# 5_In_Circuit_Debug_Interface.net
KiCad netlist of a schematic drawn in Altium Designer
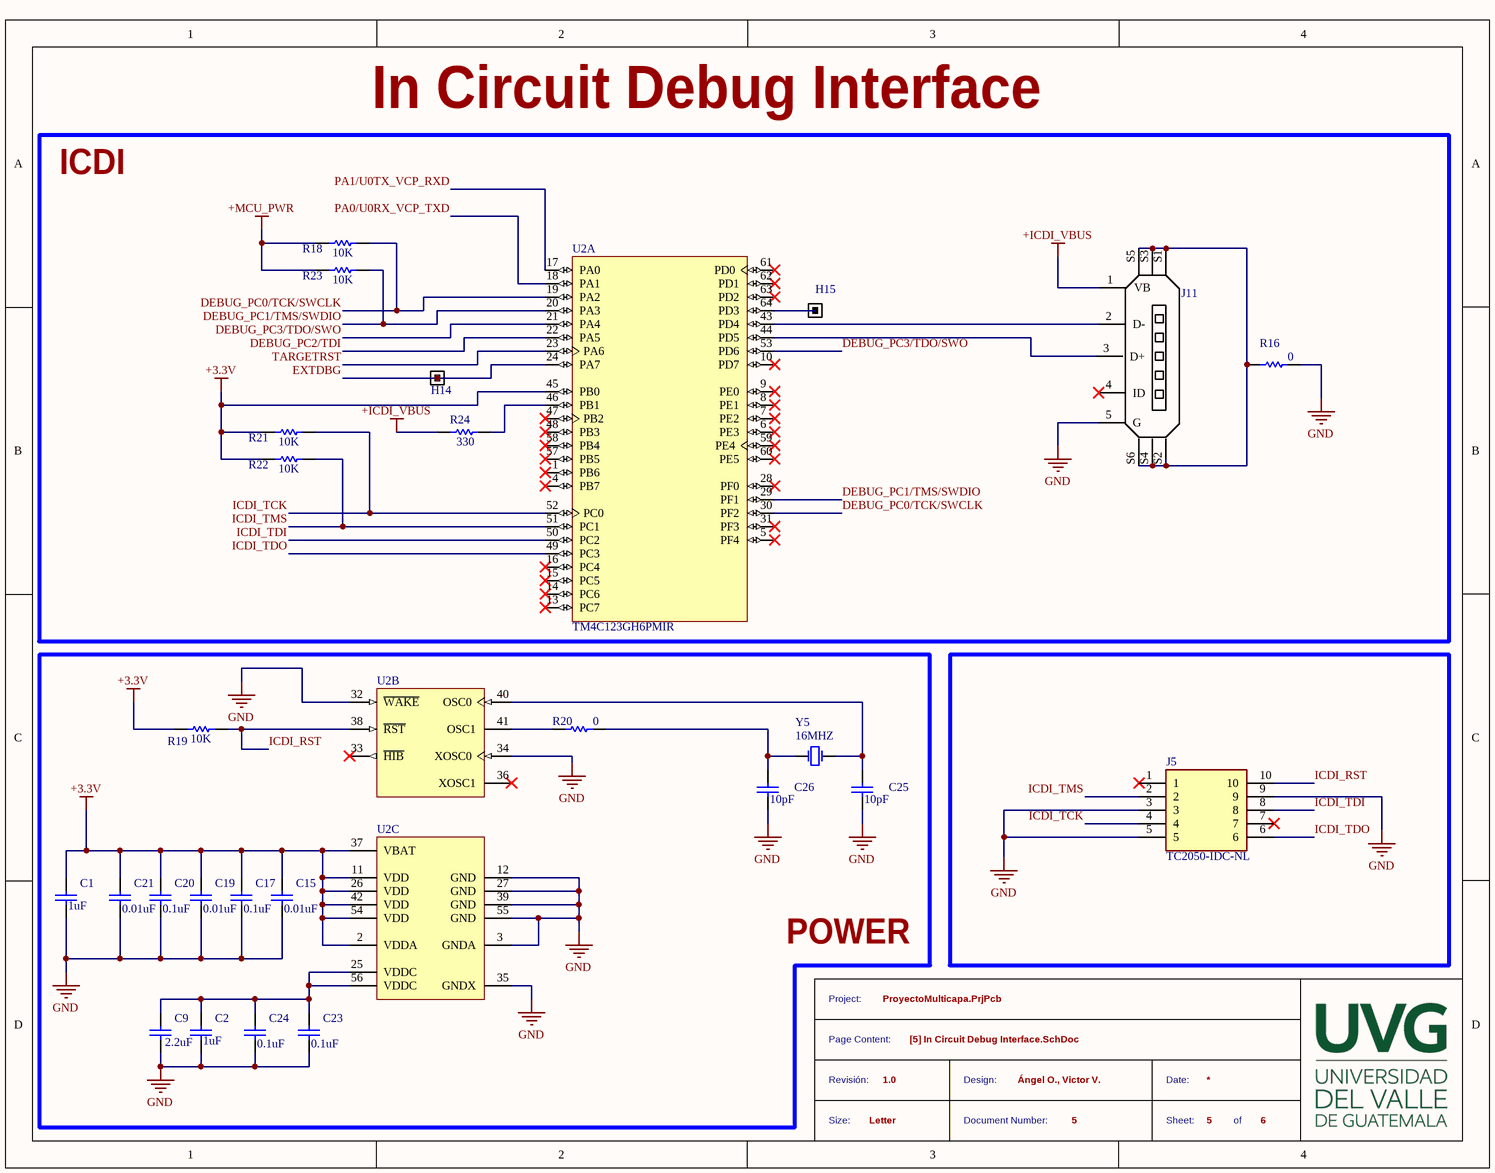
[diagram p0: [5] In Circuit Debug Interface.SchDoc]

(export (version "E")
  (design (tool "Eeschema 10.0.6"))
  (components
    (comp (ref "C1")
      (value "capacitor Johanson Dielectrics Inc")
      (footprint "C0402 imperial")
      (description "Cap Ceramic 1uF 10V X5R 10% SMD 0402 85C T/R")
      (fields
        (field (name "MANUFACTURER") "Johanson")
        (field (name "MANUFACTURER PART NUMBER") "100R07X105KV4T")
      )
      (libsource (lib "Components") (part "100R07X105KV4T"))
    )
    (comp (ref "C2")
      (value "capacitor Johanson Dielectrics Inc")
      (footprint "C0402 imperial")
      (description "Cap Ceramic 1uF 10V X5R 10% SMD 0402 85C T/R")
      (fields
        (field (name "MANUFACTURER") "Johanson")
        (field (name "MANUFACTURER PART NUMBER") "100R07X105KV4T")
      )
      (libsource (lib "Components") (part "100R07X105KV4T"))
    )
    (comp (ref "C9")
      (value "GRM188R61C225KE15D")
      (footprint "CAPC1608X90X35LL10T15")
      (description "Cap Ceramic 2.2uF 16V X5R 10% SMD 0603 85C Paper T/R")
      (fields (field (name "MANUFACTURER") "Murata") (field (name "TOLERANCE") "10%"))
      (libsource (lib "LiberiaTivaC") (part "GRM188R61C225KE15D"))
    )
    (comp (ref "C15")
      (value "EMK105B7103KV-F")
      (footprint "CAPC1005")
      (description "TAIYO YUDEN   EMK105B7103KV-F   CERAMIC CAPACITOR, 0.01UF, 16V, X7R, 10%, 0402, FULL REEL")
      (fields (field (name "MANUFACTURER") "Taiyo Yuden") (field (name "TOLERANCE") "10%"))
      (libsource (lib "LiberiaTivaC") (part "EMK105B7103KV-F"))
    )
    (comp (ref "C17")
      (value "EMK105B7104KV-F")
      (footprint "CAPC1005")
      (fields (field (name "MANUFACTURER") "Taiyo Yuden") (field (name "TOLERANCE") "10%"))
      (libsource (lib "LiberiaTivaC") (part "EMK105B7104KV-F"))
    )
    (comp (ref "C19")
      (value "EMK105B7103KV-F")
      (footprint "CAPC1005")
      (description "TAIYO YUDEN   EMK105B7103KV-F   CERAMIC CAPACITOR, 0.01UF, 16V, X7R, 10%, 0402, FULL REEL")
      (fields (field (name "MANUFACTURER") "Taiyo Yuden") (field (name "TOLERANCE") "10%"))
      (libsource (lib "LiberiaTivaC") (part "EMK105B7103KV-F"))
    )
    (comp (ref "C20")
      (value "EMK105B7104KV-F")
      (footprint "CAPC1005")
      (fields (field (name "MANUFACTURER") "Taiyo Yuden") (field (name "TOLERANCE") "10%"))
      (libsource (lib "LiberiaTivaC") (part "EMK105B7104KV-F"))
    )
    (comp (ref "C21")
      (value "EMK105B7103KV-F")
      (footprint "CAPC1005")
      (description "TAIYO YUDEN   EMK105B7103KV-F   CERAMIC CAPACITOR, 0.01UF, 16V, X7R, 10%, 0402, FULL REEL")
      (fields (field (name "MANUFACTURER") "Taiyo Yuden") (field (name "TOLERANCE") "10%"))
      (libsource (lib "LiberiaTivaC") (part "EMK105B7103KV-F"))
    )
    (comp (ref "C23")
      (value "EMK105B7104KV-F")
      (footprint "CAPC1005")
      (fields (field (name "MANUFACTURER") "Taiyo Yuden") (field (name "TOLERANCE") "10%"))
      (libsource (lib "LiberiaTivaC") (part "EMK105B7104KV-F"))
    )
    (comp (ref "C24")
      (value "EMK105B7104KV-F")
      (footprint "CAPC1005")
      (fields (field (name "MANUFACTURER") "Taiyo Yuden") (field (name "TOLERANCE") "10%"))
      (libsource (lib "LiberiaTivaC") (part "EMK105B7104KV-F"))
    )
    (comp (ref "C25")
      (value "GRM1555C1H100JZ01D")
      (footprint "CAPC1005X55X25LL05T10")
      (description "CAP, CERAMIC, 10PF, 50V, C0G/NP0, 0402")
      (fields (field (name "MANUFACTURER") "Murata") (field (name "TOLERANCE") "5%"))
      (libsource (lib "LiberiaTivaC") (part "GRM1555C1H100JZ01D"))
    )
    (comp (ref "C26")
      (value "GRM1555C1H100JZ01D")
      (footprint "CAPC1005X55X25LL05T10")
      (description "CAP, CERAMIC, 10PF, 50V, C0G/NP0, 0402")
      (fields (field (name "MANUFACTURER") "Murata") (field (name "TOLERANCE") "5%"))
      (libsource (lib "LiberiaTivaC") (part "GRM1555C1H100JZ01D"))
    )
    (comp (ref "H14")
      (value "header")
      (footprint "HEADER 1")
      (description "Pads header que aparecen en la tiva")
      (libsource (lib "LiberiaTivaC") (part "header"))
    )
    (comp (ref "H15")
      (value "header")
      (footprint "HEADER 1")
      (description "Pads header que aparecen en la tiva")
      (libsource (lib "LiberiaTivaC") (part "header"))
    )
    (comp (ref "J5")
      (value "TC2050-IDC-NL")
      (footprint "TAG-CONNECT_TC2050-IDC-NL")
      (description "Plug-Of-Nailsâ„¢ Adapter Cable")
      (fields (field (name "MF") "Tag-Connect LLC"))
      (libsource (lib "TC2050-IDC-NL") (part "TC2050-IDC-NL"))
    )
    (comp (ref "J11")
      (value "ZX62-B-5PA")
      (footprint "ZX62B5PA")
      (description "USB Connectors MICRO B RECEPT RA SMT BTTM MNT")
      (fields
        (field (name "MANUFACTURER") "Hirose")
        (field (name "MANUFACTURER PART NUMBER") "ZX62-B-5PA(11)")
      )
      (libsource (lib "LiberiaTivaC") (part "ZX62-B-5PA"))
    )
    (comp (ref "R16")
      (value "ERJ-3GEY0R00V")
      (footprint "FP-ERJ-3GEY0R00V-IPC_A")
      (description "Res Thick Film 0603 0 Ohm Jumper Molded SMD Punched Carrier T/R")
      (fields (field (name "MANUFACTURER") "Panasonic") (field (name "TOLERANCE") "0%"))
      (libsource (lib "LiberiaTivaC") (part "ERJ-3GEY0R00V"))
    )
    (comp (ref "R18")
      (value "RC0402FR-0710KL")
      (footprint "RESC1005X40X25LL05T10")
      (description "Surface Mount Thick Film Resistor, Rc Series, 10 Kohm, 62.5 Mw, - 1%, 50 V, 0402 [1005 Metric]")
      (fields (field (name "MANUFACTURER") "Yageo") (field (name "TOLERANCE") "1%"))
      (libsource (lib "LiberiaTivaC") (part "RC0402FR-0710KL"))
    )
    (comp (ref "R19")
      (value "RC0402FR-0710KL")
      (footprint "RESC1005X40X25LL05T10")
      (description "Surface Mount Thick Film Resistor, Rc Series, 10 Kohm, 62.5 Mw, - 1%, 50 V, 0402 [1005 Metric]")
      (fields (field (name "MANUFACTURER") "Yageo") (field (name "TOLERANCE") "1%"))
      (libsource (lib "LiberiaTivaC") (part "RC0402FR-0710KL"))
    )
    (comp (ref "R20")
      (value "ERJ-3GEY0R00V")
      (footprint "FP-ERJ-3GEY0R00V-IPC_A")
      (description "Res Thick Film 0603 0 Ohm Jumper Molded SMD Punched Carrier T/R")
      (fields (field (name "MANUFACTURER") "Panasonic") (field (name "TOLERANCE") "0%"))
      (libsource (lib "LiberiaTivaC") (part "ERJ-3GEY0R00V"))
    )
    (comp (ref "R21")
      (value "RC0402FR-0710KL")
      (footprint "RESC1005X40X25LL05T10")
      (description "Surface Mount Thick Film Resistor, Rc Series, 10 Kohm, 62.5 Mw, - 1%, 50 V, 0402 [1005 Metric]")
      (fields (field (name "MANUFACTURER") "Yageo") (field (name "TOLERANCE") "1%"))
      (libsource (lib "LiberiaTivaC") (part "RC0402FR-0710KL"))
    )
    (comp (ref "R22")
      (value "RC0402FR-0710KL")
      (footprint "RESC1005X40X25LL05T10")
      (description "Surface Mount Thick Film Resistor, Rc Series, 10 Kohm, 62.5 Mw, - 1%, 50 V, 0402 [1005 Metric]")
      (fields (field (name "MANUFACTURER") "Yageo") (field (name "TOLERANCE") "1%"))
      (libsource (lib "LiberiaTivaC") (part "RC0402FR-0710KL"))
    )
    (comp (ref "R23")
      (value "RC0402FR-0710KL")
      (footprint "RESC1005X40X25LL05T10")
      (description "Surface Mount Thick Film Resistor, Rc Series, 10 Kohm, 62.5 Mw, - 1%, 50 V, 0402 [1005 Metric]")
      (fields (field (name "MANUFACTURER") "Yageo") (field (name "TOLERANCE") "1%"))
      (libsource (lib "LiberiaTivaC") (part "RC0402FR-0710KL"))
    )
    (comp (ref "R24")
      (value "RC0402FR-07330RL")
      (footprint "RESC1005X40X25LL05T10")
      (description "Res Thick Film 0402 330 Ohm 1% 0.063W(1/16W) ±100ppm/C Pad SMD T/R")
      (fields (field (name "MANUFACTURER") "Yageo / Phycomp") (field (name "TOLERANCE") "1%"))
      (libsource (lib "LiberiaTivaC") (part "RC0402FR-07330RL"))
    )
    (comp (ref "U2")
      (value "TM4C123GH6PMIR")
      (footprint "PM0064A_L")
      (fields (field (name "MANUFACTURER") "Texas Instruments"))
      (libsource (lib "LiberiaTivaC") (part "TM4C123GH6PMI"))
    )
    (comp (ref "Y5")
      (value "NX5032GA-16.000000MHZ")
      (footprint "NX5032GA16000000MHZLNCD1")
      (description "CRYSTAL 16.0000MHZ 8PF SMD")
      (fields
        (field (name "MANUFACTURER_PART_NUMBER") "NX5032GA-16.000000MHZ-LN-CD-1")
        (field (name "MANUFACTURER") "NDK")
      )
      (libsource (lib "LiberiaTivaC") (part "NX5032GA-16.000000MHZ"))
    )
  )
  (nets
    (net (code "1") (name "+3.3V") (class "Default")
      (node (ref "C1") (pin "1") (pinfunction "1_1") (pintype "passive"))
      (node (ref "C15") (pin "1") (pinfunction "1_1") (pintype "passive"))
      (node (ref "C17") (pin "1") (pinfunction "1_1") (pintype "passive"))
      (node (ref "C19") (pin "1") (pinfunction "1_1") (pintype "passive"))
      (node (ref "C20") (pin "1") (pinfunction "1_1") (pintype "passive"))
      (node (ref "C21") (pin "1") (pinfunction "1_1") (pintype "passive"))
      (node (ref "R19") (pin "1") (pinfunction "1_1") (pintype "passive"))
      (node (ref "R21") (pin "1") (pinfunction "1_1") (pintype "passive"))
      (node (ref "R22") (pin "1") (pinfunction "1_1") (pintype "passive"))
      (node (ref "U2") (pin "11") (pinfunction "VDD_11") (pintype "power_in"))
      (node (ref "U2") (pin "2") (pinfunction "VDDA_2") (pintype "power_in"))
      (node (ref "U2") (pin "26") (pinfunction "VDD_26") (pintype "power_in"))
      (node (ref "U2") (pin "37") (pinfunction "VBAT_37") (pintype "power_in"))
      (node (ref "U2") (pin "42") (pinfunction "VDD_42") (pintype "power_in"))
      (node (ref "U2") (pin "45") (pinfunction "PB0_45") (pintype "bidirectional"))
      (node (ref "U2") (pin "54") (pinfunction "VDD_54") (pintype "power_in"))
    )
    (net (code "2") (name "+ICDI_VBUS") (class "Default")
      (node (ref "J11") (pin "1") (pinfunction "VB_1") (pintype "passive"))
      (node (ref "R24") (pin "1") (pinfunction "1_1") (pintype "passive"))
    )
    (net (code "3") (name "+MCU_PWR") (class "Default")
      (node (ref "R18") (pin "1") (pinfunction "1_1") (pintype "passive"))
      (node (ref "R23") (pin "1") (pinfunction "1_1") (pintype "passive"))
    )
    (net (code "4") (name "/DEBUG_PC0{slash}TCK{slash}SWCLK") (class "Default")
      (node (ref "R18") (pin "2") (pinfunction "2_2") (pintype "passive"))
      (node (ref "U2") (pin "19") (pinfunction "PA2_19") (pintype "bidirectional"))
      (node (ref "U2") (pin "30") (pinfunction "PF2_30") (pintype "bidirectional"))
    )
    (net (code "5") (name "/DEBUG_PC1{slash}TMS{slash}SWDIO") (class "Default")
      (node (ref "R23") (pin "2") (pinfunction "2_2") (pintype "passive"))
      (node (ref "U2") (pin "20") (pinfunction "PA3_20") (pintype "bidirectional"))
      (node (ref "U2") (pin "29") (pinfunction "PF1_29") (pintype "bidirectional"))
    )
    (net (code "6") (name "/DEBUG_PC2{slash}TDI") (class "Default")
      (node (ref "U2") (pin "22") (pinfunction "PA5_22") (pintype "bidirectional"))
    )
    (net (code "7") (name "/DEBUG_PC3{slash}TDO{slash}SWO") (class "Default")
      (node (ref "U2") (pin "21") (pinfunction "PA4_21") (pintype "bidirectional"))
      (node (ref "U2") (pin "53") (pinfunction "PD6_53") (pintype "bidirectional"))
    )
    (net (code "8") (name "/EXTDBG") (class "Default")
      (node (ref "H14") (pin "1") (pinfunction "1_1") (pintype "passive"))
      (node (ref "U2") (pin "24") (pinfunction "PA7_24") (pintype "bidirectional"))
    )
    (net (code "9") (name "/ICDI_RST") (class "Default")
      (node (ref "J5") (pin "10") (pinfunction "10_10") (pintype "passive"))
      (node (ref "R19") (pin "2") (pinfunction "2_2") (pintype "passive"))
      (node (ref "U2") (pin "38") (pinfunction "~{RST}_38") (pintype "input"))
    )
    (net (code "10") (name "/ICDI_TCK") (class "Default")
      (node (ref "J5") (pin "4") (pinfunction "4_4") (pintype "passive"))
      (node (ref "R21") (pin "2") (pinfunction "2_2") (pintype "passive"))
      (node (ref "U2") (pin "52") (pinfunction "PC0_52") (pintype "bidirectional"))
    )
    (net (code "11") (name "/ICDI_TDI") (class "Default")
      (node (ref "J5") (pin "8") (pinfunction "8_8") (pintype "passive"))
      (node (ref "U2") (pin "50") (pinfunction "PC2_50") (pintype "bidirectional"))
    )
    (net (code "12") (name "/ICDI_TDO") (class "Default")
      (node (ref "J5") (pin "6") (pinfunction "6_6") (pintype "passive"))
      (node (ref "U2") (pin "49") (pinfunction "PC3_49") (pintype "bidirectional"))
    )
    (net (code "13") (name "/ICDI_TMS") (class "Default")
      (node (ref "J5") (pin "2") (pinfunction "2_2") (pintype "passive"))
      (node (ref "R22") (pin "2") (pinfunction "2_2") (pintype "passive"))
      (node (ref "U2") (pin "51") (pinfunction "PC1_51") (pintype "bidirectional"))
    )
    (net (code "14") (name "/PA0{slash}U0RX_VCP_TXD") (class "Default")
      (node (ref "U2") (pin "18") (pinfunction "PA1_18") (pintype "bidirectional"))
    )
    (net (code "15") (name "/PA1{slash}U0TX_VCP_RXD") (class "Default")
      (node (ref "U2") (pin "17") (pinfunction "PA0_17") (pintype "bidirectional"))
    )
    (net (code "16") (name "/TARGETRST") (class "Default")
      (node (ref "U2") (pin "23") (pinfunction "PA6_23") (pintype "bidirectional"))
    )
    (net (code "17") (name "GND") (class "Default")
      (node (ref "C1") (pin "2") (pinfunction "2_2") (pintype "passive"))
      (node (ref "C15") (pin "2") (pinfunction "2_2") (pintype "passive"))
      (node (ref "C17") (pin "2") (pinfunction "2_2") (pintype "passive"))
      (node (ref "C19") (pin "2") (pinfunction "2_2") (pintype "passive"))
      (node (ref "C2") (pin "2") (pinfunction "2_2") (pintype "passive"))
      (node (ref "C20") (pin "2") (pinfunction "2_2") (pintype "passive"))
      (node (ref "C21") (pin "2") (pinfunction "2_2") (pintype "passive"))
      (node (ref "C23") (pin "2") (pinfunction "2_2") (pintype "passive"))
      (node (ref "C24") (pin "2") (pinfunction "2_2") (pintype "passive"))
      (node (ref "C25") (pin "2") (pinfunction "2_2") (pintype "passive"))
      (node (ref "C26") (pin "2") (pinfunction "2_2") (pintype "passive"))
      (node (ref "C9") (pin "2") (pinfunction "2_2") (pintype "passive"))
      (node (ref "J11") (pin "5") (pinfunction "G_5") (pintype "passive"))
      (node (ref "J5") (pin "3") (pinfunction "3_3") (pintype "passive"))
      (node (ref "J5") (pin "5") (pinfunction "5_5") (pintype "passive"))
      (node (ref "J5") (pin "9") (pinfunction "9_9") (pintype "passive"))
      (node (ref "R16") (pin "2") (pinfunction "2_2") (pintype "passive"))
      (node (ref "U2") (pin "12") (pinfunction "GND_12") (pintype "power_in"))
      (node (ref "U2") (pin "27") (pinfunction "GND_27") (pintype "power_in"))
      (node (ref "U2") (pin "3") (pinfunction "GNDA_3") (pintype "power_in"))
      (node (ref "U2") (pin "32") (pinfunction "~{WAKE}_32") (pintype "input"))
      (node (ref "U2") (pin "34") (pinfunction "XOSC0_34") (pintype "input"))
      (node (ref "U2") (pin "35") (pinfunction "GNDX_35") (pintype "power_in"))
      (node (ref "U2") (pin "39") (pinfunction "GND_39") (pintype "power_in"))
      (node (ref "U2") (pin "55") (pinfunction "GND_55") (pintype "power_in"))
    )
    (net (code "18") (name "Net-(C2-Pad1)") (class "Default")
      (node (ref "C2") (pin "1") (pinfunction "1_1") (pintype "passive"))
      (node (ref "C23") (pin "1") (pinfunction "1_1") (pintype "passive"))
      (node (ref "C24") (pin "1") (pinfunction "1_1") (pintype "passive"))
      (node (ref "C9") (pin "1") (pinfunction "1_1") (pintype "passive"))
      (node (ref "U2") (pin "25") (pinfunction "VDDC_25") (pintype "power_in"))
      (node (ref "U2") (pin "56") (pinfunction "VDDC_56") (pintype "power_in"))
    )
    (net (code "19") (name "Net-(C26-Pad1)") (class "Default")
      (node (ref "C26") (pin "1") (pinfunction "1_1") (pintype "passive"))
      (node (ref "R20") (pin "2") (pinfunction "2_2") (pintype "passive"))
      (node (ref "Y5") (pin "1") (pinfunction "1_1") (pintype "passive"))
    )
    (net (code "20") (name "Net-(J11-D+)") (class "Default")
      (node (ref "J11") (pin "3") (pinfunction "D+_3") (pintype "passive"))
      (node (ref "U2") (pin "44") (pinfunction "PD5_44") (pintype "bidirectional"))
    )
    (net (code "21") (name "Net-(J11-D-)") (class "Default")
      (node (ref "J11") (pin "2") (pinfunction "D-_2") (pintype "passive"))
      (node (ref "U2") (pin "43") (pinfunction "PD4_43") (pintype "bidirectional"))
    )
    (net (code "22") (name "Net-(J11-PadS1)") (class "Default")
      (node (ref "J11") (pin "S1") (pinfunction "S1_S1") (pintype "passive"))
      (node (ref "J11") (pin "S2") (pinfunction "S2_S2") (pintype "passive"))
      (node (ref "J11") (pin "S3") (pinfunction "S3_S3") (pintype "passive"))
      (node (ref "J11") (pin "S4") (pinfunction "S4_S4") (pintype "passive"))
      (node (ref "J11") (pin "S5") (pinfunction "S5_S5") (pintype "passive"))
      (node (ref "J11") (pin "S6") (pinfunction "S6_S6") (pintype "passive"))
      (node (ref "R16") (pin "1") (pinfunction "1_1") (pintype "passive"))
    )
    (net (code "23") (name "Net-(U2A-PB1)") (class "Default")
      (node (ref "R24") (pin "2") (pinfunction "2_2") (pintype "passive"))
      (node (ref "U2") (pin "46") (pinfunction "PB1_46") (pintype "bidirectional"))
    )
    (net (code "24") (name "Net-(U2A-PD3)") (class "Default")
      (node (ref "H15") (pin "1") (pinfunction "1_1") (pintype "passive"))
      (node (ref "U2") (pin "64") (pinfunction "PD3_64") (pintype "bidirectional"))
    )
    (net (code "25") (name "Net-(U2B-OSC0)") (class "Default")
      (node (ref "C25") (pin "1") (pinfunction "1_1") (pintype "passive"))
      (node (ref "U2") (pin "40") (pinfunction "OSC0_40") (pintype "input"))
      (node (ref "Y5") (pin "2") (pinfunction "2_2") (pintype "passive"))
    )
    (net (code "26") (name "Net-(U2B-OSC1)") (class "Default")
      (node (ref "R20") (pin "1") (pinfunction "1_1") (pintype "passive"))
      (node (ref "U2") (pin "41") (pinfunction "OSC1_41") (pintype "passive"))
    )
    (net (code "27") (name "unconnected-(J5-Pad1)") (class "Default")
      (node (ref "J5") (pin "1") (pinfunction "1_1") (pintype "passive+no_connect"))
    )
    (net (code "28") (name "unconnected-(J5-Pad7)") (class "Default")
      (node (ref "J5") (pin "7") (pinfunction "7_7") (pintype "passive+no_connect"))
    )
    (net (code "29") (name "unconnected-(J11-ID-Pad4)") (class "Default")
      (node (ref "J11") (pin "4") (pinfunction "ID_4") (pintype "passive+no_connect"))
    )
    (net (code "30") (name "unconnected-(U2A-PB2-Pad47)") (class "Default")
      (node (ref "U2") (pin "47") (pinfunction "PB2_47") (pintype "bidirectional+no_connect"))
    )
    (net (code "31") (name "unconnected-(U2A-PB3-Pad48)") (class "Default")
      (node (ref "U2") (pin "48") (pinfunction "PB3_48") (pintype "bidirectional+no_connect"))
    )
    (net (code "32") (name "unconnected-(U2A-PB4-Pad58)") (class "Default")
      (node (ref "U2") (pin "58") (pinfunction "PB4_58") (pintype "bidirectional+no_connect"))
    )
    (net (code "33") (name "unconnected-(U2A-PB5-Pad57)") (class "Default")
      (node (ref "U2") (pin "57") (pinfunction "PB5_57") (pintype "bidirectional+no_connect"))
    )
    (net (code "34") (name "unconnected-(U2A-PB6-Pad1)") (class "Default")
      (node (ref "U2") (pin "1") (pinfunction "PB6_1") (pintype "bidirectional+no_connect"))
    )
    (net (code "35") (name "unconnected-(U2A-PB7-Pad4)") (class "Default")
      (node (ref "U2") (pin "4") (pinfunction "PB7_4") (pintype "bidirectional+no_connect"))
    )
    (net (code "36") (name "unconnected-(U2A-PC4-Pad16)") (class "Default")
      (node (ref "U2") (pin "16") (pinfunction "PC4_16") (pintype "bidirectional+no_connect"))
    )
    (net (code "37") (name "unconnected-(U2A-PC5-Pad15)") (class "Default")
      (node (ref "U2") (pin "15") (pinfunction "PC5_15") (pintype "bidirectional+no_connect"))
    )
    (net (code "38") (name "unconnected-(U2A-PC6-Pad14)") (class "Default")
      (node (ref "U2") (pin "14") (pinfunction "PC6_14") (pintype "bidirectional+no_connect"))
    )
    (net (code "39") (name "unconnected-(U2A-PC7-Pad13)") (class "Default")
      (node (ref "U2") (pin "13") (pinfunction "PC7_13") (pintype "bidirectional+no_connect"))
    )
    (net (code "40") (name "unconnected-(U2A-PD0-Pad61)") (class "Default")
      (node (ref "U2") (pin "61") (pinfunction "PD0_61") (pintype "bidirectional+no_connect"))
    )
    (net (code "41") (name "unconnected-(U2A-PD1-Pad62)") (class "Default")
      (node (ref "U2") (pin "62") (pinfunction "PD1_62") (pintype "bidirectional+no_connect"))
    )
    (net (code "42") (name "unconnected-(U2A-PD2-Pad63)") (class "Default")
      (node (ref "U2") (pin "63") (pinfunction "PD2_63") (pintype "bidirectional+no_connect"))
    )
    (net (code "43") (name "unconnected-(U2A-PD7-Pad10)") (class "Default")
      (node (ref "U2") (pin "10") (pinfunction "PD7_10") (pintype "bidirectional+no_connect"))
    )
    (net (code "44") (name "unconnected-(U2A-PE0-Pad9)") (class "Default")
      (node (ref "U2") (pin "9") (pinfunction "PE0_9") (pintype "bidirectional+no_connect"))
    )
    (net (code "45") (name "unconnected-(U2A-PE1-Pad8)") (class "Default")
      (node (ref "U2") (pin "8") (pinfunction "PE1_8") (pintype "bidirectional+no_connect"))
    )
    (net (code "46") (name "unconnected-(U2A-PE2-Pad7)") (class "Default")
      (node (ref "U2") (pin "7") (pinfunction "PE2_7") (pintype "bidirectional+no_connect"))
    )
    (net (code "47") (name "unconnected-(U2A-PE3-Pad6)") (class "Default")
      (node (ref "U2") (pin "6") (pinfunction "PE3_6") (pintype "bidirectional+no_connect"))
    )
    (net (code "48") (name "unconnected-(U2A-PE4-Pad59)") (class "Default")
      (node (ref "U2") (pin "59") (pinfunction "PE4_59") (pintype "bidirectional+no_connect"))
    )
    (net (code "49") (name "unconnected-(U2A-PE5-Pad60)") (class "Default")
      (node (ref "U2") (pin "60") (pinfunction "PE5_60") (pintype "bidirectional+no_connect"))
    )
    (net (code "50") (name "unconnected-(U2A-PF0-Pad28)") (class "Default")
      (node (ref "U2") (pin "28") (pinfunction "PF0_28") (pintype "bidirectional+no_connect"))
    )
    (net (code "51") (name "unconnected-(U2A-PF3-Pad31)") (class "Default")
      (node (ref "U2") (pin "31") (pinfunction "PF3_31") (pintype "bidirectional+no_connect"))
    )
    (net (code "52") (name "unconnected-(U2A-PF4-Pad5)") (class "Default")
      (node (ref "U2") (pin "5") (pinfunction "PF4_5") (pintype "bidirectional+no_connect"))
    )
    (net (code "53") (name "unconnected-(U2B-XOSC1-Pad36)") (class "Default")
      (node (ref "U2") (pin "36") (pinfunction "XOSC1_36") (pintype "passive+no_connect"))
    )
    (net (code "54") (name "unconnected-(U2B-~{HIB}-Pad33)") (class "Default")
      (node (ref "U2") (pin "33") (pinfunction "~{HIB}_33") (pintype "output+no_connect"))
    )
  )
)
